# TeensyAmp_R4_2b.net
KiCad netlist of a schematic drawn in EAGLE
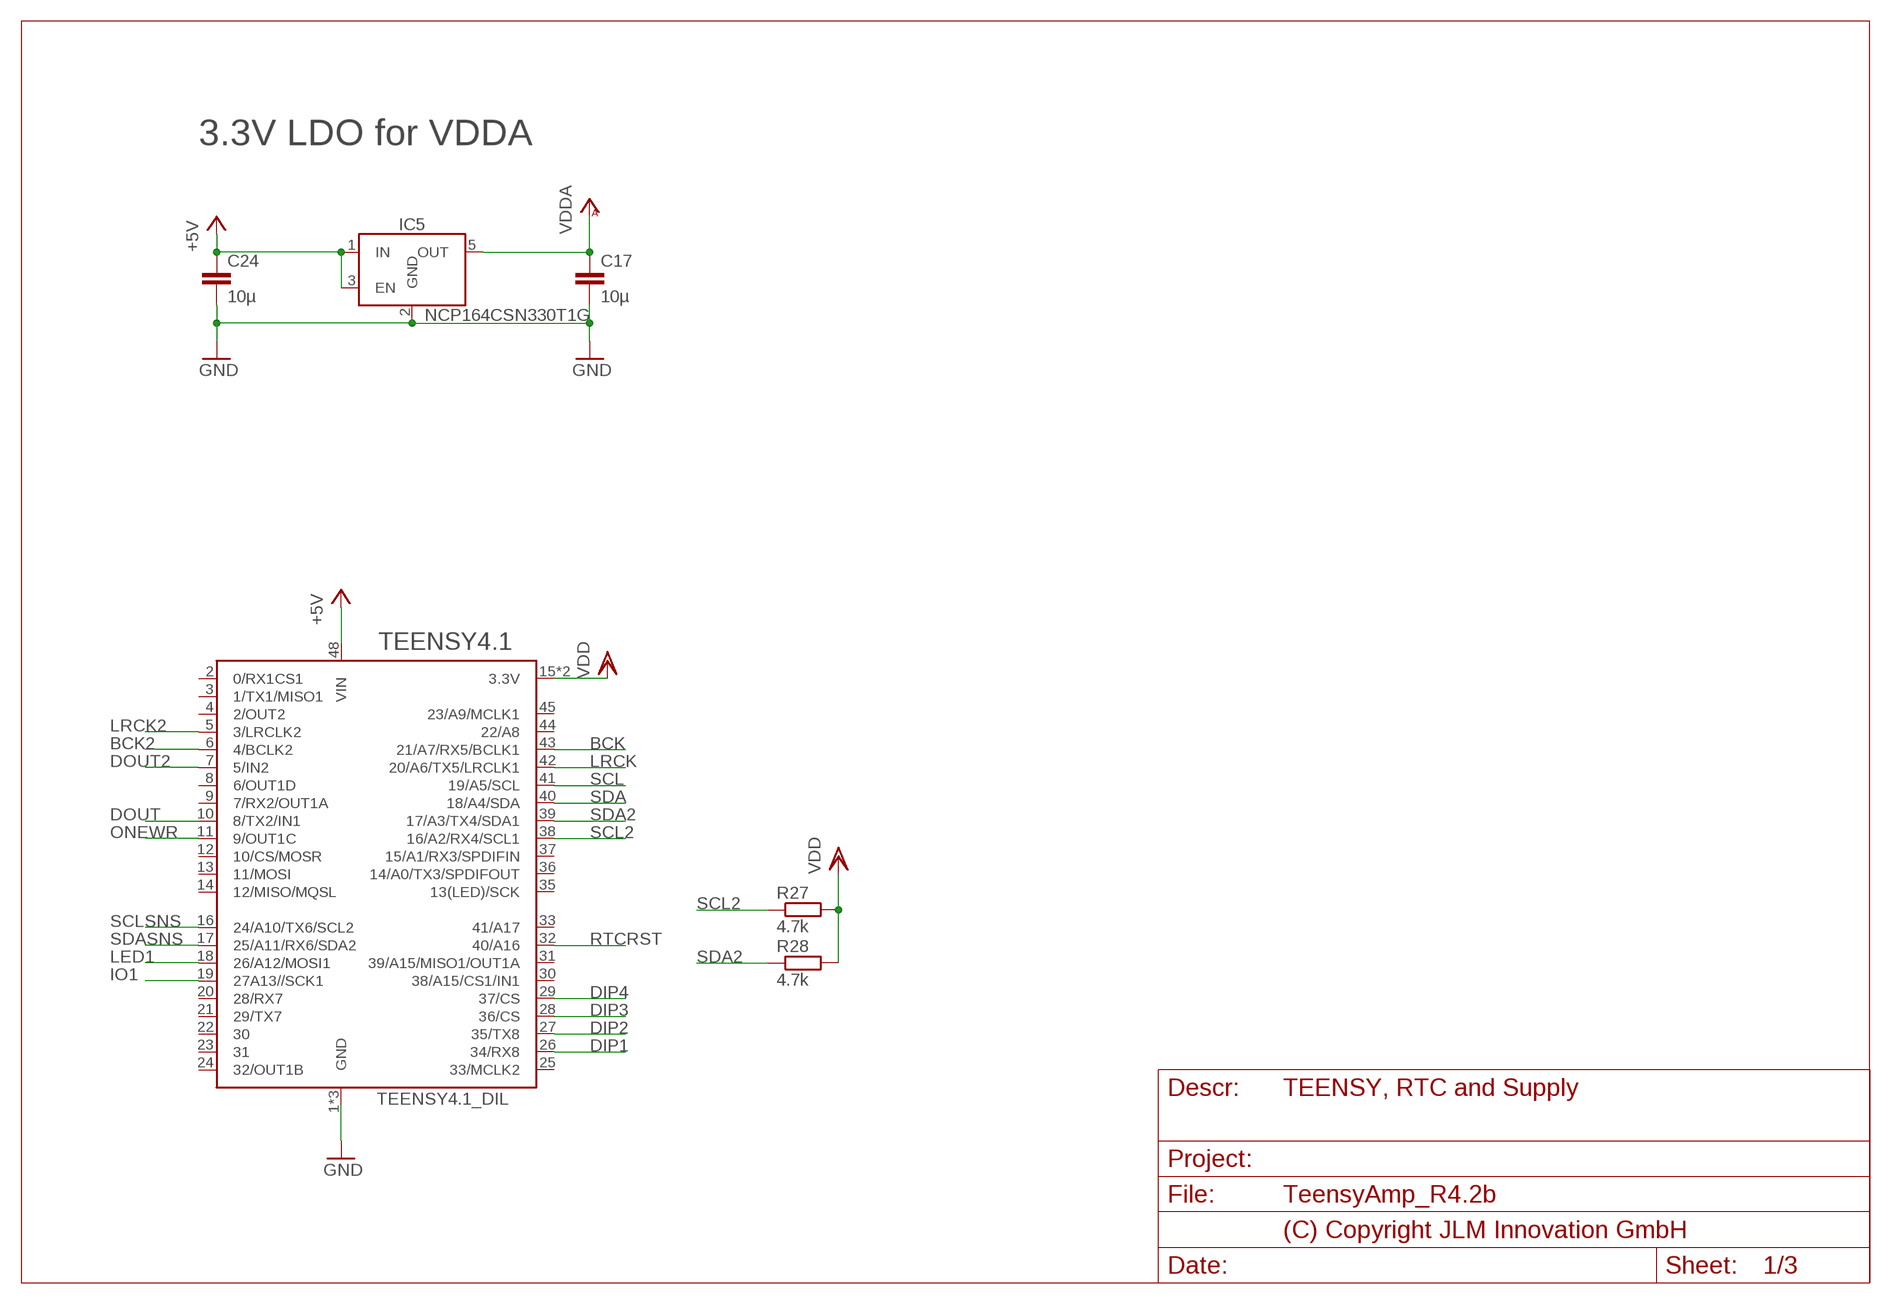
[diagram p0: schematic, sheet 1]
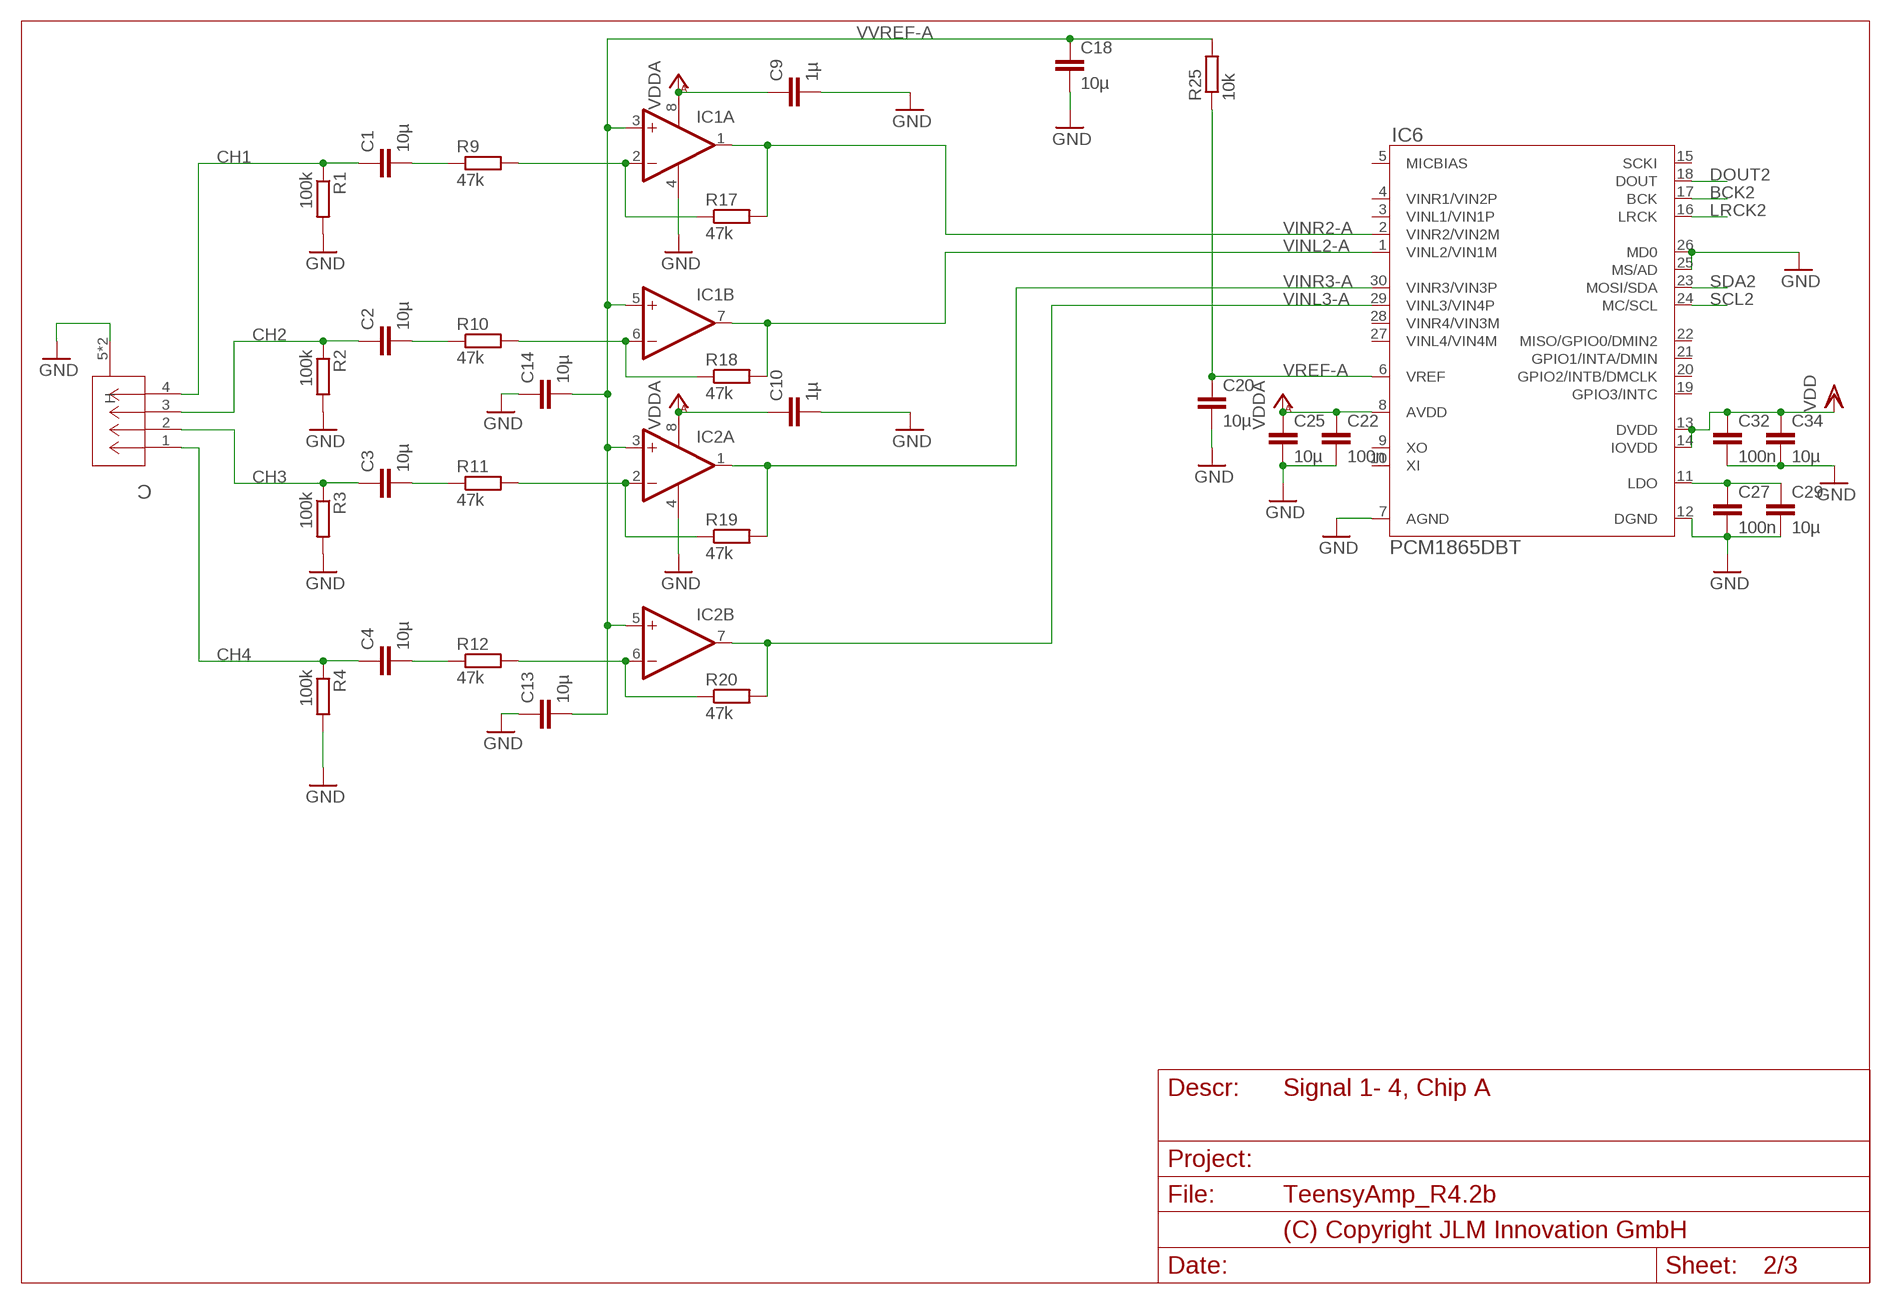
[diagram p1: schematic, sheet 2]
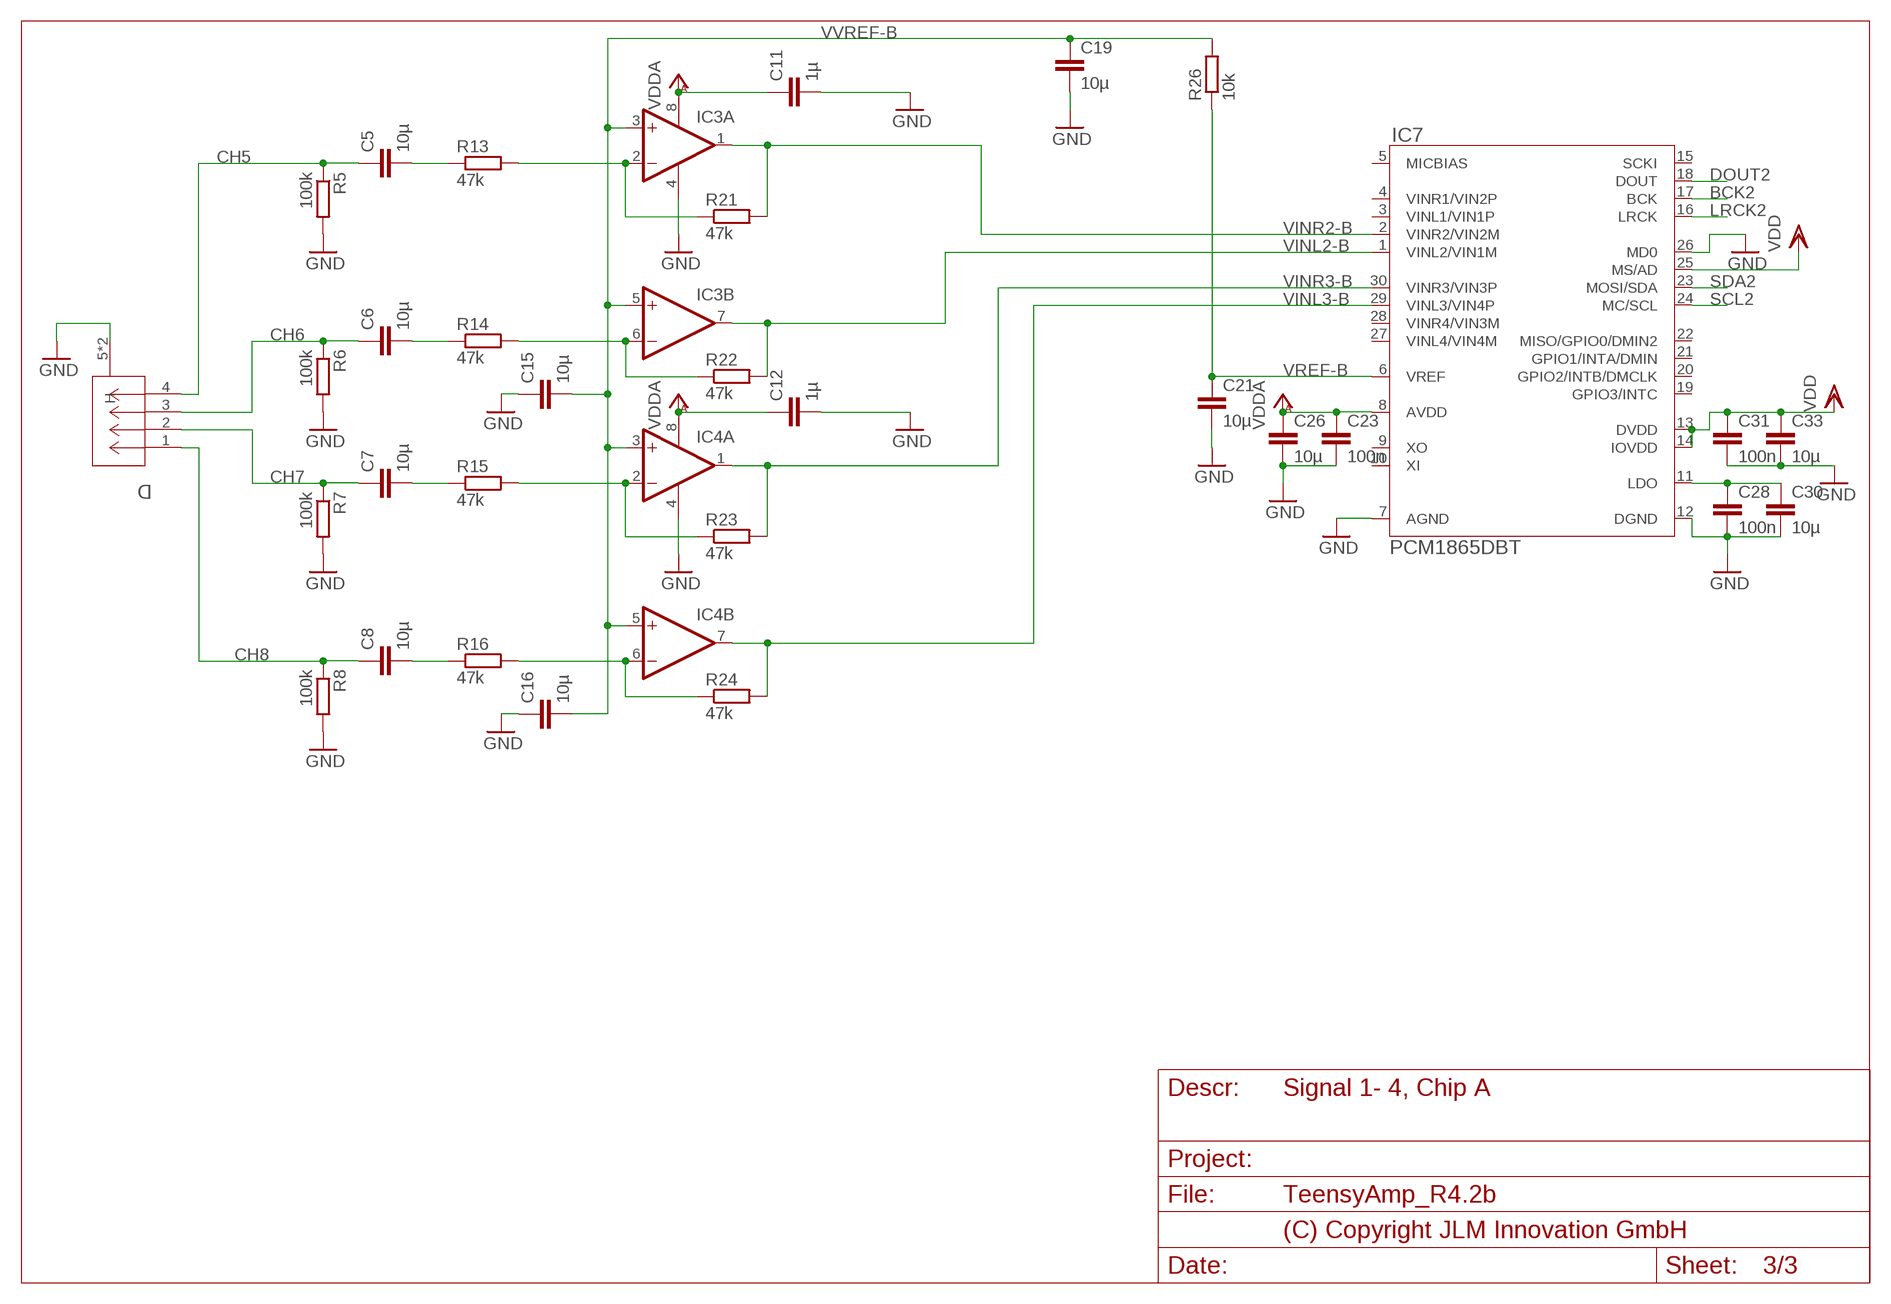
[diagram p2: schematic, sheet 3]

(export (version "E")
  (design (tool "Eeschema 10.0.6"))
  (components
    (comp (ref "C17")
      (value "10µ")
      (footprint "eagle-import:C0603")
      (libsource (lib "eagle-import") (part "C-EUC0603"))
    )
    (comp (ref "C24")
      (value "10µ")
      (footprint "eagle-import:C0603")
      (libsource (lib "eagle-import") (part "C-EUC0603"))
    )
    (comp (ref "IC5")
      (value "NCP164CSN330T1G")
      (footprint "eagle-import:SOT23-5")
      (libsource (lib "eagle-import") (part "LDO_ENSOT23-5"))
    )
    (comp (ref "R27")
      (value "4.7k")
      (footprint "eagle-import:R0603")
      (libsource (lib "eagle-import") (part "R_JLMR0603"))
    )
    (comp (ref "R28")
      (value "4.7k")
      (footprint "eagle-import:R0603")
      (libsource (lib "eagle-import") (part "R_JLMR0603"))
    )
    (comp (ref "TEENSY4.1")
      (value "TEENSY4.1_DIL")
      (footprint "eagle-import:TEENSY4.1_DIL")
      (libsource (lib "eagle-import") (part "TEENSY4.1_DIL"))
    )
    (comp (ref "C")
      (value "5055670471")
      (footprint "eagle-import:CONN04_5055670471_MOL")
      (fields (field (name "COPYRIGHT") "Copyright (C) 2025 Ultra Librarian. All rights reserved."))
      (libsource (lib "eagle-import") (part "5055670471"))
    )
    (comp (ref "C1")
      (value "10µ")
      (footprint "eagle-import:C0805")
      (libsource (lib "eagle-import") (part "C-EUC0805"))
    )
    (comp (ref "C2")
      (value "10µ")
      (footprint "eagle-import:C0805")
      (libsource (lib "eagle-import") (part "C-EUC0805"))
    )
    (comp (ref "C3")
      (value "10µ")
      (footprint "eagle-import:C0805")
      (libsource (lib "eagle-import") (part "C-EUC0805"))
    )
    (comp (ref "C4")
      (value "10µ")
      (footprint "eagle-import:C0805")
      (libsource (lib "eagle-import") (part "C-EUC0805"))
    )
    (comp (ref "C9")
      (value "1µ")
      (footprint "eagle-import:C0603")
      (libsource (lib "eagle-import") (part "C-EUC0603"))
    )
    (comp (ref "C10")
      (value "1µ")
      (footprint "eagle-import:C0603")
      (libsource (lib "eagle-import") (part "C-EUC0603"))
    )
    (comp (ref "C13")
      (value "10µ")
      (footprint "eagle-import:C0603")
      (libsource (lib "eagle-import") (part "C-EUC0603"))
    )
    (comp (ref "C14")
      (value "10µ")
      (footprint "eagle-import:C0603")
      (libsource (lib "eagle-import") (part "C-EUC0603"))
    )
    (comp (ref "C18")
      (value "10µ")
      (footprint "eagle-import:C0603")
      (libsource (lib "eagle-import") (part "C-EUC0603"))
    )
    (comp (ref "C20")
      (value "10µ")
      (footprint "eagle-import:C0603")
      (libsource (lib "eagle-import") (part "C-EUC0603"))
    )
    (comp (ref "C22")
      (value "100n")
      (footprint "eagle-import:C0603")
      (libsource (lib "eagle-import") (part "C-EUC0603"))
    )
    (comp (ref "C25")
      (value "10µ")
      (footprint "eagle-import:C0603")
      (libsource (lib "eagle-import") (part "C-EUC0603"))
    )
    (comp (ref "C27")
      (value "100n")
      (footprint "eagle-import:C0603")
      (libsource (lib "eagle-import") (part "C-EUC0603"))
    )
    (comp (ref "C29")
      (value "10µ")
      (footprint "eagle-import:C0603")
      (libsource (lib "eagle-import") (part "C-EUC0603"))
    )
    (comp (ref "C32")
      (value "100n")
      (footprint "eagle-import:C0603")
      (libsource (lib "eagle-import") (part "C-EUC0603"))
    )
    (comp (ref "C34")
      (value "10µ")
      (footprint "eagle-import:C0603")
      (libsource (lib "eagle-import") (part "C-EUC0603"))
    )
    (comp (ref "IC1")
      (value "OPA2344E")
      (footprint "eagle-import:MSOP08")
      (libsource (lib "eagle-import") (part "OPA2E344"))
    )
    (comp (ref "IC2")
      (value "OPA2344E")
      (footprint "eagle-import:MSOP08")
      (libsource (lib "eagle-import") (part "OPA2E344"))
    )
    (comp (ref "IC6")
      (value "PCM1865DBT")
      (footprint "eagle-import:SOP50P640X120-30N")
      (libsource (lib "eagle-import") (part "PCM1865DBT"))
    )
    (comp (ref "R1")
      (value "100k")
      (footprint "eagle-import:R0603")
      (libsource (lib "eagle-import") (part "R_JLMR0603"))
    )
    (comp (ref "R2")
      (value "100k")
      (footprint "eagle-import:R0603")
      (libsource (lib "eagle-import") (part "R_JLMR0603"))
    )
    (comp (ref "R3")
      (value "100k")
      (footprint "eagle-import:R0603")
      (libsource (lib "eagle-import") (part "R_JLMR0603"))
    )
    (comp (ref "R4")
      (value "100k")
      (footprint "eagle-import:R0603")
      (libsource (lib "eagle-import") (part "R_JLMR0603"))
    )
    (comp (ref "R9")
      (value "47k")
      (footprint "eagle-import:R0603")
      (libsource (lib "eagle-import") (part "R_JLMR0603"))
    )
    (comp (ref "R10")
      (value "47k")
      (footprint "eagle-import:R0603")
      (libsource (lib "eagle-import") (part "R_JLMR0603"))
    )
    (comp (ref "R11")
      (value "47k")
      (footprint "eagle-import:R0603")
      (libsource (lib "eagle-import") (part "R_JLMR0603"))
    )
    (comp (ref "R12")
      (value "47k")
      (footprint "eagle-import:R0603")
      (libsource (lib "eagle-import") (part "R_JLMR0603"))
    )
    (comp (ref "R17")
      (value "47k")
      (footprint "eagle-import:R0603")
      (libsource (lib "eagle-import") (part "R_JLMR0603"))
    )
    (comp (ref "R18")
      (value "47k")
      (footprint "eagle-import:R0603")
      (libsource (lib "eagle-import") (part "R_JLMR0603"))
    )
    (comp (ref "R19")
      (value "47k")
      (footprint "eagle-import:R0603")
      (libsource (lib "eagle-import") (part "R_JLMR0603"))
    )
    (comp (ref "R20")
      (value "47k")
      (footprint "eagle-import:R0603")
      (libsource (lib "eagle-import") (part "R_JLMR0603"))
    )
    (comp (ref "R25")
      (value "10k")
      (footprint "eagle-import:R0603")
      (libsource (lib "eagle-import") (part "R_JLMR0603"))
    )
    (comp (ref "C5")
      (value "10µ")
      (footprint "eagle-import:C0805")
      (libsource (lib "eagle-import") (part "C-EUC0805"))
    )
    (comp (ref "C6")
      (value "10µ")
      (footprint "eagle-import:C0805")
      (libsource (lib "eagle-import") (part "C-EUC0805"))
    )
    (comp (ref "C7")
      (value "10µ")
      (footprint "eagle-import:C0805")
      (libsource (lib "eagle-import") (part "C-EUC0805"))
    )
    (comp (ref "C8")
      (value "10µ")
      (footprint "eagle-import:C0805")
      (libsource (lib "eagle-import") (part "C-EUC0805"))
    )
    (comp (ref "C11")
      (value "1µ")
      (footprint "eagle-import:C0603")
      (libsource (lib "eagle-import") (part "C-EUC0603"))
    )
    (comp (ref "C12")
      (value "1µ")
      (footprint "eagle-import:C0603")
      (libsource (lib "eagle-import") (part "C-EUC0603"))
    )
    (comp (ref "C15")
      (value "10µ")
      (footprint "eagle-import:C0603")
      (libsource (lib "eagle-import") (part "C-EUC0603"))
    )
    (comp (ref "C16")
      (value "10µ")
      (footprint "eagle-import:C0603")
      (libsource (lib "eagle-import") (part "C-EUC0603"))
    )
    (comp (ref "C19")
      (value "10µ")
      (footprint "eagle-import:C0603")
      (libsource (lib "eagle-import") (part "C-EUC0603"))
    )
    (comp (ref "C21")
      (value "10µ")
      (footprint "eagle-import:C0603")
      (libsource (lib "eagle-import") (part "C-EUC0603"))
    )
    (comp (ref "C23")
      (value "100n")
      (footprint "eagle-import:C0603")
      (libsource (lib "eagle-import") (part "C-EUC0603"))
    )
    (comp (ref "C26")
      (value "10µ")
      (footprint "eagle-import:C0603")
      (libsource (lib "eagle-import") (part "C-EUC0603"))
    )
    (comp (ref "C28")
      (value "100n")
      (footprint "eagle-import:C0603")
      (libsource (lib "eagle-import") (part "C-EUC0603"))
    )
    (comp (ref "C30")
      (value "10µ")
      (footprint "eagle-import:C0603")
      (libsource (lib "eagle-import") (part "C-EUC0603"))
    )
    (comp (ref "C31")
      (value "100n")
      (footprint "eagle-import:C0603")
      (libsource (lib "eagle-import") (part "C-EUC0603"))
    )
    (comp (ref "C33")
      (value "10µ")
      (footprint "eagle-import:C0603")
      (libsource (lib "eagle-import") (part "C-EUC0603"))
    )
    (comp (ref "D")
      (value "5055670471")
      (footprint "eagle-import:CONN04_5055670471_MOL")
      (fields (field (name "COPYRIGHT") "Copyright (C) 2025 Ultra Librarian. All rights reserved."))
      (libsource (lib "eagle-import") (part "5055670471"))
    )
    (comp (ref "IC3")
      (value "OPA2344E")
      (footprint "eagle-import:MSOP08")
      (libsource (lib "eagle-import") (part "OPA2E344"))
    )
    (comp (ref "IC4")
      (value "OPA2344E")
      (footprint "eagle-import:MSOP08")
      (libsource (lib "eagle-import") (part "OPA2E344"))
    )
    (comp (ref "IC7")
      (value "PCM1865DBT")
      (footprint "eagle-import:SOP50P640X120-30N")
      (libsource (lib "eagle-import") (part "PCM1865DBT"))
    )
    (comp (ref "R5")
      (value "100k")
      (footprint "eagle-import:R0603")
      (libsource (lib "eagle-import") (part "R_JLMR0603"))
    )
    (comp (ref "R6")
      (value "100k")
      (footprint "eagle-import:R0603")
      (libsource (lib "eagle-import") (part "R_JLMR0603"))
    )
    (comp (ref "R7")
      (value "100k")
      (footprint "eagle-import:R0603")
      (libsource (lib "eagle-import") (part "R_JLMR0603"))
    )
    (comp (ref "R8")
      (value "100k")
      (footprint "eagle-import:R0603")
      (libsource (lib "eagle-import") (part "R_JLMR0603"))
    )
    (comp (ref "R13")
      (value "47k")
      (footprint "eagle-import:R0603")
      (libsource (lib "eagle-import") (part "R_JLMR0603"))
    )
    (comp (ref "R14")
      (value "47k")
      (footprint "eagle-import:R0603")
      (libsource (lib "eagle-import") (part "R_JLMR0603"))
    )
    (comp (ref "R15")
      (value "47k")
      (footprint "eagle-import:R0603")
      (libsource (lib "eagle-import") (part "R_JLMR0603"))
    )
    (comp (ref "R16")
      (value "47k")
      (footprint "eagle-import:R0603")
      (libsource (lib "eagle-import") (part "R_JLMR0603"))
    )
    (comp (ref "R21")
      (value "47k")
      (footprint "eagle-import:R0603")
      (libsource (lib "eagle-import") (part "R_JLMR0603"))
    )
    (comp (ref "R22")
      (value "47k")
      (footprint "eagle-import:R0603")
      (libsource (lib "eagle-import") (part "R_JLMR0603"))
    )
    (comp (ref "R23")
      (value "47k")
      (footprint "eagle-import:R0603")
      (libsource (lib "eagle-import") (part "R_JLMR0603"))
    )
    (comp (ref "R24")
      (value "47k")
      (footprint "eagle-import:R0603")
      (libsource (lib "eagle-import") (part "R_JLMR0603"))
    )
    (comp (ref "R26")
      (value "10k")
      (footprint "eagle-import:R0603")
      (libsource (lib "eagle-import") (part "R_JLMR0603"))
    )
  )
  (nets
    (net (code "1") (name "+5V") (class "Default")
      (node (ref "C24") (pin "1") (pinfunction "1_1") (pintype "passive"))
      (node (ref "IC5") (pin "1") (pinfunction "IN_1") (pintype "input"))
      (node (ref "IC5") (pin "3") (pinfunction "EN_3") (pintype "input"))
      (node (ref "TEENSY4.1") (pin "48") (pinfunction "VIN_48") (pintype "power_in"))
    )
    (net (code "2") (name "BCK") (class "Default")
      (node (ref "TEENSY4.1") (pin "43") (pinfunction "21/A7/RX5/BCLK1_43") (pintype "bidirectional"))
    )
    (net (code "3") (name "BCK2") (class "Default")
      (node (ref "IC6") (pin "17") (pinfunction "BCK_17") (pintype "bidirectional"))
      (node (ref "IC7") (pin "17") (pinfunction "BCK_17") (pintype "bidirectional"))
      (node (ref "TEENSY4.1") (pin "6") (pinfunction "4/BCLK2_6") (pintype "bidirectional"))
    )
    (net (code "4") (name "CH1") (class "Default")
      (node (ref "C") (pin "4") (pinfunction "4_4") (pintype "passive"))
      (node (ref "C1") (pin "1") (pinfunction "1_1") (pintype "passive"))
      (node (ref "R1") (pin "1") (pinfunction "1_1") (pintype "passive"))
    )
    (net (code "5") (name "CH2") (class "Default")
      (node (ref "C") (pin "3") (pinfunction "3_3") (pintype "passive"))
      (node (ref "C2") (pin "1") (pinfunction "1_1") (pintype "passive"))
      (node (ref "R2") (pin "1") (pinfunction "1_1") (pintype "passive"))
    )
    (net (code "6") (name "CH3") (class "Default")
      (node (ref "C") (pin "2") (pinfunction "2_2") (pintype "passive"))
      (node (ref "C3") (pin "1") (pinfunction "1_1") (pintype "passive"))
      (node (ref "R3") (pin "1") (pinfunction "1_1") (pintype "passive"))
    )
    (net (code "7") (name "CH4") (class "Default")
      (node (ref "C") (pin "1") (pinfunction "1_1") (pintype "passive"))
      (node (ref "C4") (pin "1") (pinfunction "1_1") (pintype "passive"))
      (node (ref "R4") (pin "1") (pinfunction "1_1") (pintype "passive"))
    )
    (net (code "8") (name "CH5") (class "Default")
      (node (ref "C5") (pin "1") (pinfunction "1_1") (pintype "passive"))
      (node (ref "D") (pin "4") (pinfunction "4_4") (pintype "passive"))
      (node (ref "R5") (pin "1") (pinfunction "1_1") (pintype "passive"))
    )
    (net (code "9") (name "CH6") (class "Default")
      (node (ref "C6") (pin "1") (pinfunction "1_1") (pintype "passive"))
      (node (ref "D") (pin "3") (pinfunction "3_3") (pintype "passive"))
      (node (ref "R6") (pin "1") (pinfunction "1_1") (pintype "passive"))
    )
    (net (code "10") (name "CH7") (class "Default")
      (node (ref "C7") (pin "1") (pinfunction "1_1") (pintype "passive"))
      (node (ref "D") (pin "2") (pinfunction "2_2") (pintype "passive"))
      (node (ref "R7") (pin "1") (pinfunction "1_1") (pintype "passive"))
    )
    (net (code "11") (name "CH8") (class "Default")
      (node (ref "C8") (pin "1") (pinfunction "1_1") (pintype "passive"))
      (node (ref "D") (pin "1") (pinfunction "1_1") (pintype "passive"))
      (node (ref "R8") (pin "1") (pinfunction "1_1") (pintype "passive"))
    )
    (net (code "12") (name "DIP1") (class "Default")
      (node (ref "TEENSY4.1") (pin "26") (pinfunction "34/RX8_26") (pintype "bidirectional"))
    )
    (net (code "13") (name "DIP2") (class "Default")
      (node (ref "TEENSY4.1") (pin "27") (pinfunction "35/TX8_27") (pintype "bidirectional"))
    )
    (net (code "14") (name "DIP3") (class "Default")
      (node (ref "TEENSY4.1") (pin "28") (pinfunction "36/CS_28") (pintype "bidirectional"))
    )
    (net (code "15") (name "DIP4") (class "Default")
      (node (ref "TEENSY4.1") (pin "29") (pinfunction "37/CS_29") (pintype "bidirectional"))
    )
    (net (code "16") (name "DOUT") (class "Default")
      (node (ref "TEENSY4.1") (pin "10") (pinfunction "8/TX2/IN1_10") (pintype "bidirectional"))
    )
    (net (code "17") (name "DOUT2") (class "Default")
      (node (ref "IC6") (pin "18") (pinfunction "DOUT_18") (pintype "output"))
      (node (ref "IC7") (pin "18") (pinfunction "DOUT_18") (pintype "output"))
      (node (ref "TEENSY4.1") (pin "7") (pinfunction "5/IN2_7") (pintype "bidirectional"))
    )
    (net (code "18") (name "GND") (class "Default")
      (node (ref "C") (pin "5") (pinfunction "H_5") (pintype "passive"))
      (node (ref "C") (pin "6") (pinfunction "H_6") (pintype "passive"))
      (node (ref "C10") (pin "2") (pinfunction "2_2") (pintype "passive"))
      (node (ref "C11") (pin "2") (pinfunction "2_2") (pintype "passive"))
      (node (ref "C12") (pin "2") (pinfunction "2_2") (pintype "passive"))
      (node (ref "C13") (pin "1") (pinfunction "1_1") (pintype "passive"))
      (node (ref "C14") (pin "1") (pinfunction "1_1") (pintype "passive"))
      (node (ref "C15") (pin "1") (pinfunction "1_1") (pintype "passive"))
      (node (ref "C16") (pin "1") (pinfunction "1_1") (pintype "passive"))
      (node (ref "C17") (pin "2") (pinfunction "2_2") (pintype "passive"))
      (node (ref "C18") (pin "2") (pinfunction "2_2") (pintype "passive"))
      (node (ref "C19") (pin "2") (pinfunction "2_2") (pintype "passive"))
      (node (ref "C20") (pin "2") (pinfunction "2_2") (pintype "passive"))
      (node (ref "C21") (pin "2") (pinfunction "2_2") (pintype "passive"))
      (node (ref "C22") (pin "2") (pinfunction "2_2") (pintype "passive"))
      (node (ref "C23") (pin "2") (pinfunction "2_2") (pintype "passive"))
      (node (ref "C24") (pin "2") (pinfunction "2_2") (pintype "passive"))
      (node (ref "C25") (pin "2") (pinfunction "2_2") (pintype "passive"))
      (node (ref "C26") (pin "2") (pinfunction "2_2") (pintype "passive"))
      (node (ref "C27") (pin "2") (pinfunction "2_2") (pintype "passive"))
      (node (ref "C28") (pin "2") (pinfunction "2_2") (pintype "passive"))
      (node (ref "C29") (pin "2") (pinfunction "2_2") (pintype "passive"))
      (node (ref "C30") (pin "2") (pinfunction "2_2") (pintype "passive"))
      (node (ref "C31") (pin "2") (pinfunction "2_2") (pintype "passive"))
      (node (ref "C32") (pin "2") (pinfunction "2_2") (pintype "passive"))
      (node (ref "C33") (pin "2") (pinfunction "2_2") (pintype "passive"))
      (node (ref "C34") (pin "2") (pinfunction "2_2") (pintype "passive"))
      (node (ref "C9") (pin "2") (pinfunction "2_2") (pintype "passive"))
      (node (ref "D") (pin "5") (pinfunction "H_5") (pintype "passive"))
      (node (ref "D") (pin "6") (pinfunction "H_6") (pintype "passive"))
      (node (ref "IC1") (pin "4") (pinfunction "V-_4") (pintype "power_in"))
      (node (ref "IC2") (pin "4") (pinfunction "V-_4") (pintype "power_in"))
      (node (ref "IC3") (pin "4") (pinfunction "V-_4") (pintype "power_in"))
      (node (ref "IC4") (pin "4") (pinfunction "V-_4") (pintype "power_in"))
      (node (ref "IC5") (pin "2") (pinfunction "GND_2") (pintype "power_in"))
      (node (ref "IC6") (pin "12") (pinfunction "DGND_12") (pintype "power_in"))
      (node (ref "IC6") (pin "25") (pinfunction "MS/AD_25") (pintype "input"))
      (node (ref "IC6") (pin "26") (pinfunction "MD0_26") (pintype "input"))
      (node (ref "IC6") (pin "7") (pinfunction "AGND_7") (pintype "power_in"))
      (node (ref "IC7") (pin "12") (pinfunction "DGND_12") (pintype "power_in"))
      (node (ref "IC7") (pin "26") (pinfunction "MD0_26") (pintype "input"))
      (node (ref "IC7") (pin "7") (pinfunction "AGND_7") (pintype "power_in"))
      (node (ref "R1") (pin "2") (pinfunction "2_2") (pintype "passive"))
      (node (ref "R2") (pin "2") (pinfunction "2_2") (pintype "passive"))
      (node (ref "R3") (pin "2") (pinfunction "2_2") (pintype "passive"))
      (node (ref "R4") (pin "2") (pinfunction "2_2") (pintype "passive"))
      (node (ref "R5") (pin "2") (pinfunction "2_2") (pintype "passive"))
      (node (ref "R6") (pin "2") (pinfunction "2_2") (pintype "passive"))
      (node (ref "R7") (pin "2") (pinfunction "2_2") (pintype "passive"))
      (node (ref "R8") (pin "2") (pinfunction "2_2") (pintype "passive"))
      (node (ref "TEENSY4.1") (pin "1") (pinfunction "GND_1") (pintype "power_in"))
      (node (ref "TEENSY4.1") (pin "34") (pinfunction "GND_34") (pintype "power_in"))
      (node (ref "TEENSY4.1") (pin "47") (pinfunction "GND_47") (pintype "power_in"))
    )
    (net (code "19") (name "IO1") (class "Default")
      (node (ref "TEENSY4.1") (pin "19") (pinfunction "27A13//SCK1_19") (pintype "bidirectional"))
    )
    (net (code "20") (name "LED1") (class "Default")
      (node (ref "TEENSY4.1") (pin "18") (pinfunction "26/A12/MOSI1_18") (pintype "bidirectional"))
    )
    (net (code "21") (name "LRCK") (class "Default")
      (node (ref "TEENSY4.1") (pin "42") (pinfunction "20/A6/TX5/LRCLK1_42") (pintype "bidirectional"))
    )
    (net (code "22") (name "LRCK2") (class "Default")
      (node (ref "IC6") (pin "16") (pinfunction "LRCK_16") (pintype "bidirectional"))
      (node (ref "IC7") (pin "16") (pinfunction "LRCK_16") (pintype "bidirectional"))
      (node (ref "TEENSY4.1") (pin "5") (pinfunction "3/LRCLK2_5") (pintype "bidirectional"))
    )
    (net (code "23") (name "Net-(C1-Pad2)") (class "Default")
      (node (ref "C1") (pin "2") (pinfunction "2_2") (pintype "passive"))
      (node (ref "R9") (pin "1") (pinfunction "1_1") (pintype "passive"))
    )
    (net (code "24") (name "Net-(C2-Pad2)") (class "Default")
      (node (ref "C2") (pin "2") (pinfunction "2_2") (pintype "passive"))
      (node (ref "R10") (pin "1") (pinfunction "1_1") (pintype "passive"))
    )
    (net (code "25") (name "Net-(C3-Pad2)") (class "Default")
      (node (ref "C3") (pin "2") (pinfunction "2_2") (pintype "passive"))
      (node (ref "R11") (pin "1") (pinfunction "1_1") (pintype "passive"))
    )
    (net (code "26") (name "Net-(C4-Pad2)") (class "Default")
      (node (ref "C4") (pin "2") (pinfunction "2_2") (pintype "passive"))
      (node (ref "R12") (pin "1") (pinfunction "1_1") (pintype "passive"))
    )
    (net (code "27") (name "Net-(C5-Pad2)") (class "Default")
      (node (ref "C5") (pin "2") (pinfunction "2_2") (pintype "passive"))
      (node (ref "R13") (pin "1") (pinfunction "1_1") (pintype "passive"))
    )
    (net (code "28") (name "Net-(C6-Pad2)") (class "Default")
      (node (ref "C6") (pin "2") (pinfunction "2_2") (pintype "passive"))
      (node (ref "R14") (pin "1") (pinfunction "1_1") (pintype "passive"))
    )
    (net (code "29") (name "Net-(C7-Pad2)") (class "Default")
      (node (ref "C7") (pin "2") (pinfunction "2_2") (pintype "passive"))
      (node (ref "R15") (pin "1") (pinfunction "1_1") (pintype "passive"))
    )
    (net (code "30") (name "Net-(C8-Pad2)") (class "Default")
      (node (ref "C8") (pin "2") (pinfunction "2_2") (pintype "passive"))
      (node (ref "R16") (pin "1") (pinfunction "1_1") (pintype "passive"))
    )
    (net (code "31") (name "Net-(IC1A--IN)") (class "Default")
      (node (ref "IC1") (pin "2") (pinfunction "-IN_2") (pintype "input"))
      (node (ref "R17") (pin "1") (pinfunction "1_1") (pintype "passive"))
      (node (ref "R9") (pin "2") (pinfunction "2_2") (pintype "passive"))
    )
    (net (code "32") (name "Net-(IC1B--IN)") (class "Default")
      (node (ref "IC1") (pin "6") (pinfunction "-IN_6") (pintype "input"))
      (node (ref "R10") (pin "2") (pinfunction "2_2") (pintype "passive"))
      (node (ref "R18") (pin "1") (pinfunction "1_1") (pintype "passive"))
    )
    (net (code "33") (name "Net-(IC2A--IN)") (class "Default")
      (node (ref "IC2") (pin "2") (pinfunction "-IN_2") (pintype "input"))
      (node (ref "R11") (pin "2") (pinfunction "2_2") (pintype "passive"))
      (node (ref "R19") (pin "1") (pinfunction "1_1") (pintype "passive"))
    )
    (net (code "34") (name "Net-(IC2B--IN)") (class "Default")
      (node (ref "IC2") (pin "6") (pinfunction "-IN_6") (pintype "input"))
      (node (ref "R12") (pin "2") (pinfunction "2_2") (pintype "passive"))
      (node (ref "R20") (pin "1") (pinfunction "1_1") (pintype "passive"))
    )
    (net (code "35") (name "Net-(IC3A--IN)") (class "Default")
      (node (ref "IC3") (pin "2") (pinfunction "-IN_2") (pintype "input"))
      (node (ref "R13") (pin "2") (pinfunction "2_2") (pintype "passive"))
      (node (ref "R21") (pin "1") (pinfunction "1_1") (pintype "passive"))
    )
    (net (code "36") (name "Net-(IC3B--IN)") (class "Default")
      (node (ref "IC3") (pin "6") (pinfunction "-IN_6") (pintype "input"))
      (node (ref "R14") (pin "2") (pinfunction "2_2") (pintype "passive"))
      (node (ref "R22") (pin "1") (pinfunction "1_1") (pintype "passive"))
    )
    (net (code "37") (name "Net-(IC4A--IN)") (class "Default")
      (node (ref "IC4") (pin "2") (pinfunction "-IN_2") (pintype "input"))
      (node (ref "R15") (pin "2") (pinfunction "2_2") (pintype "passive"))
      (node (ref "R23") (pin "1") (pinfunction "1_1") (pintype "passive"))
    )
    (net (code "38") (name "Net-(IC4B--IN)") (class "Default")
      (node (ref "IC4") (pin "6") (pinfunction "-IN_6") (pintype "input"))
      (node (ref "R16") (pin "2") (pinfunction "2_2") (pintype "passive"))
      (node (ref "R24") (pin "1") (pinfunction "1_1") (pintype "passive"))
    )
    (net (code "39") (name "Net-(IC6-LDO)") (class "Default")
      (node (ref "C27") (pin "1") (pinfunction "1_1") (pintype "passive"))
      (node (ref "C29") (pin "1") (pinfunction "1_1") (pintype "passive"))
      (node (ref "IC6") (pin "11") (pinfunction "LDO_11") (pintype "bidirectional"))
    )
    (net (code "40") (name "Net-(IC7-LDO)") (class "Default")
      (node (ref "C28") (pin "1") (pinfunction "1_1") (pintype "passive"))
      (node (ref "C30") (pin "1") (pinfunction "1_1") (pintype "passive"))
      (node (ref "IC7") (pin "11") (pinfunction "LDO_11") (pintype "bidirectional"))
    )
    (net (code "41") (name "ONEWR") (class "Default")
      (node (ref "TEENSY4.1") (pin "11") (pinfunction "9/OUT1C_11") (pintype "bidirectional"))
    )
    (net (code "42") (name "RTCRST") (class "Default")
      (node (ref "TEENSY4.1") (pin "32") (pinfunction "40/A16_32") (pintype "bidirectional"))
    )
    (net (code "43") (name "SCL") (class "Default")
      (node (ref "TEENSY4.1") (pin "41") (pinfunction "19/A5/SCL_41") (pintype "bidirectional"))
    )
    (net (code "44") (name "SCL2") (class "Default")
      (node (ref "IC6") (pin "24") (pinfunction "MC/SCL_24") (pintype "input"))
      (node (ref "IC7") (pin "24") (pinfunction "MC/SCL_24") (pintype "input"))
      (node (ref "R27") (pin "1") (pinfunction "1_1") (pintype "passive"))
      (node (ref "TEENSY4.1") (pin "38") (pinfunction "16/A2/RX4/SCL1_38") (pintype "bidirectional"))
    )
    (net (code "45") (name "SCLSNS") (class "Default")
      (node (ref "TEENSY4.1") (pin "16") (pinfunction "24/A10/TX6/SCL2_16") (pintype "bidirectional"))
    )
    (net (code "46") (name "SDA") (class "Default")
      (node (ref "TEENSY4.1") (pin "40") (pinfunction "18/A4/SDA_40") (pintype "bidirectional"))
    )
    (net (code "47") (name "SDA2") (class "Default")
      (node (ref "IC6") (pin "23") (pinfunction "MOSI/SDA_23") (pintype "bidirectional"))
      (node (ref "IC7") (pin "23") (pinfunction "MOSI/SDA_23") (pintype "bidirectional"))
      (node (ref "R28") (pin "1") (pinfunction "1_1") (pintype "passive"))
      (node (ref "TEENSY4.1") (pin "39") (pinfunction "17/A3/TX4/SDA1_39") (pintype "bidirectional"))
    )
    (net (code "48") (name "SDASNS") (class "Default")
      (node (ref "TEENSY4.1") (pin "17") (pinfunction "25/A11/RX6/SDA2_17") (pintype "bidirectional"))
    )
    (net (code "49") (name "VDD") (class "Default")
      (node (ref "C31") (pin "1") (pinfunction "1_1") (pintype "passive"))
      (node (ref "C32") (pin "1") (pinfunction "1_1") (pintype "passive"))
      (node (ref "C33") (pin "1") (pinfunction "1_1") (pintype "passive"))
      (node (ref "C34") (pin "1") (pinfunction "1_1") (pintype "passive"))
      (node (ref "IC6") (pin "13") (pinfunction "DVDD_13") (pintype "power_in"))
      (node (ref "IC6") (pin "14") (pinfunction "IOVDD_14") (pintype "power_in"))
      (node (ref "IC7") (pin "13") (pinfunction "DVDD_13") (pintype "power_in"))
      (node (ref "IC7") (pin "14") (pinfunction "IOVDD_14") (pintype "power_in"))
      (node (ref "IC7") (pin "25") (pinfunction "MS/AD_25") (pintype "input"))
      (node (ref "R27") (pin "2") (pinfunction "2_2") (pintype "passive"))
      (node (ref "R28") (pin "2") (pinfunction "2_2") (pintype "passive"))
      (node (ref "TEENSY4.1") (pin "15") (pinfunction "3.3V_15") (pintype "output"))
      (node (ref "TEENSY4.1") (pin "46") (pinfunction "3.3V_46") (pintype "output"))
    )
    (net (code "50") (name "VDDA") (class "Default")
      (node (ref "C10") (pin "1") (pinfunction "1_1") (pintype "passive"))
      (node (ref "C11") (pin "1") (pinfunction "1_1") (pintype "passive"))
      (node (ref "C12") (pin "1") (pinfunction "1_1") (pintype "passive"))
      (node (ref "C17") (pin "1") (pinfunction "1_1") (pintype "passive"))
      (node (ref "C22") (pin "1") (pinfunction "1_1") (pintype "passive"))
      (node (ref "C23") (pin "1") (pinfunction "1_1") (pintype "passive"))
      (node (ref "C25") (pin "1") (pinfunction "1_1") (pintype "passive"))
      (node (ref "C26") (pin "1") (pinfunction "1_1") (pintype "passive"))
      (node (ref "C9") (pin "1") (pinfunction "1_1") (pintype "passive"))
      (node (ref "IC1") (pin "8") (pinfunction "V+_8") (pintype "power_in"))
      (node (ref "IC2") (pin "8") (pinfunction "V+_8") (pintype "power_in"))
      (node (ref "IC3") (pin "8") (pinfunction "V+_8") (pintype "power_in"))
      (node (ref "IC4") (pin "8") (pinfunction "V+_8") (pintype "power_in"))
      (node (ref "IC5") (pin "5") (pinfunction "OUT_5") (pintype "output"))
      (node (ref "IC6") (pin "8") (pinfunction "AVDD_8") (pintype "power_in"))
      (node (ref "IC7") (pin "8") (pinfunction "AVDD_8") (pintype "power_in"))
    )
    (net (code "51") (name "VINL2-A") (class "Default")
      (node (ref "IC1") (pin "7") (pinfunction "OUT_7") (pintype "output"))
      (node (ref "IC6") (pin "1") (pinfunction "VINL2/VIN1M_1") (pintype "input"))
      (node (ref "R18") (pin "2") (pinfunction "2_2") (pintype "passive"))
    )
    (net (code "52") (name "VINL2-B") (class "Default")
      (node (ref "IC3") (pin "7") (pinfunction "OUT_7") (pintype "output"))
      (node (ref "IC7") (pin "1") (pinfunction "VINL2/VIN1M_1") (pintype "input"))
      (node (ref "R22") (pin "2") (pinfunction "2_2") (pintype "passive"))
    )
    (net (code "53") (name "VINL3-A") (class "Default")
      (node (ref "IC2") (pin "7") (pinfunction "OUT_7") (pintype "output"))
      (node (ref "IC6") (pin "29") (pinfunction "VINL3/VIN4P_29") (pintype "input"))
      (node (ref "R20") (pin "2") (pinfunction "2_2") (pintype "passive"))
    )
    (net (code "54") (name "VINL3-B") (class "Default")
      (node (ref "IC4") (pin "7") (pinfunction "OUT_7") (pintype "output"))
      (node (ref "IC7") (pin "29") (pinfunction "VINL3/VIN4P_29") (pintype "input"))
      (node (ref "R24") (pin "2") (pinfunction "2_2") (pintype "passive"))
    )
    (net (code "55") (name "VINR2-A") (class "Default")
      (node (ref "IC1") (pin "1") (pinfunction "OUT_1") (pintype "output"))
      (node (ref "IC6") (pin "2") (pinfunction "VINR2/VIN2M_2") (pintype "input"))
      (node (ref "R17") (pin "2") (pinfunction "2_2") (pintype "passive"))
    )
    (net (code "56") (name "VINR2-B") (class "Default")
      (node (ref "IC3") (pin "1") (pinfunction "OUT_1") (pintype "output"))
      (node (ref "IC7") (pin "2") (pinfunction "VINR2/VIN2M_2") (pintype "input"))
      (node (ref "R21") (pin "2") (pinfunction "2_2") (pintype "passive"))
    )
    (net (code "57") (name "VINR3-A") (class "Default")
      (node (ref "IC2") (pin "1") (pinfunction "OUT_1") (pintype "output"))
      (node (ref "IC6") (pin "30") (pinfunction "VINR3/VIN3P_30") (pintype "input"))
      (node (ref "R19") (pin "2") (pinfunction "2_2") (pintype "passive"))
    )
    (net (code "58") (name "VINR3-B") (class "Default")
      (node (ref "IC4") (pin "1") (pinfunction "OUT_1") (pintype "output"))
      (node (ref "IC7") (pin "30") (pinfunction "VINR3/VIN3P_30") (pintype "input"))
      (node (ref "R23") (pin "2") (pinfunction "2_2") (pintype "passive"))
    )
    (net (code "59") (name "VREF-A") (class "Default")
      (node (ref "C20") (pin "1") (pinfunction "1_1") (pintype "passive"))
      (node (ref "IC6") (pin "6") (pinfunction "VREF_6") (pintype "output"))
      (node (ref "R25") (pin "1") (pinfunction "1_1") (pintype "passive"))
    )
    (net (code "60") (name "VREF-B") (class "Default")
      (node (ref "C21") (pin "1") (pinfunction "1_1") (pintype "passive"))
      (node (ref "IC7") (pin "6") (pinfunction "VREF_6") (pintype "output"))
      (node (ref "R26") (pin "1") (pinfunction "1_1") (pintype "passive"))
    )
    (net (code "61") (name "VVREF-A") (class "Default")
      (node (ref "C13") (pin "2") (pinfunction "2_2") (pintype "passive"))
      (node (ref "C14") (pin "2") (pinfunction "2_2") (pintype "passive"))
      (node (ref "C18") (pin "1") (pinfunction "1_1") (pintype "passive"))
      (node (ref "IC1") (pin "3") (pinfunction "+IN_3") (pintype "input"))
      (node (ref "IC1") (pin "5") (pinfunction "+IN_5") (pintype "input"))
      (node (ref "IC2") (pin "3") (pinfunction "+IN_3") (pintype "input"))
      (node (ref "IC2") (pin "5") (pinfunction "+IN_5") (pintype "input"))
      (node (ref "R25") (pin "2") (pinfunction "2_2") (pintype "passive"))
    )
    (net (code "62") (name "VVREF-B") (class "Default")
      (node (ref "C15") (pin "2") (pinfunction "2_2") (pintype "passive"))
      (node (ref "C16") (pin "2") (pinfunction "2_2") (pintype "passive"))
      (node (ref "C19") (pin "1") (pinfunction "1_1") (pintype "passive"))
      (node (ref "IC3") (pin "3") (pinfunction "+IN_3") (pintype "input"))
      (node (ref "IC3") (pin "5") (pinfunction "+IN_5") (pintype "input"))
      (node (ref "IC4") (pin "3") (pinfunction "+IN_3") (pintype "input"))
      (node (ref "IC4") (pin "5") (pinfunction "+IN_5") (pintype "input"))
      (node (ref "R26") (pin "2") (pinfunction "2_2") (pintype "passive"))
    )
    (net (code "63") (name "unconnected-(IC6-GPIO1{slash}INTA{slash}DMIN-Pad21)") (class "Default")
      (node (ref "IC6") (pin "21") (pinfunction "GPIO1/INTA/DMIN_21") (pintype "bidirectional"))
    )
    (net (code "64") (name "unconnected-(IC6-GPIO2{slash}INTB{slash}DMCLK-Pad20)") (class "Default")
      (node (ref "IC6") (pin "20") (pinfunction "GPIO2/INTB/DMCLK_20") (pintype "bidirectional"))
    )
    (net (code "65") (name "unconnected-(IC6-GPIO3{slash}INTC-Pad19)") (class "Default")
      (node (ref "IC6") (pin "19") (pinfunction "GPIO3/INTC_19") (pintype "bidirectional"))
    )
    (net (code "66") (name "unconnected-(IC6-MICBIAS-Pad5)") (class "Default")
      (node (ref "IC6") (pin "5") (pinfunction "MICBIAS_5") (pintype "input"))
    )
    (net (code "67") (name "unconnected-(IC6-MISO{slash}GPIO0{slash}DMIN2-Pad22)") (class "Default")
      (node (ref "IC6") (pin "22") (pinfunction "MISO/GPIO0/DMIN2_22") (pintype "bidirectional"))
    )
    (net (code "68") (name "unconnected-(IC6-SCKI-Pad15)") (class "Default")
      (node (ref "IC6") (pin "15") (pinfunction "SCKI_15") (pintype "input"))
    )
    (net (code "69") (name "unconnected-(IC6-VINL1{slash}VIN1P-Pad3)") (class "Default")
      (node (ref "IC6") (pin "3") (pinfunction "VINL1/VIN1P_3") (pintype "input"))
    )
    (net (code "70") (name "unconnected-(IC6-VINL4{slash}VIN4M-Pad27)") (class "Default")
      (node (ref "IC6") (pin "27") (pinfunction "VINL4/VIN4M_27") (pintype "input"))
    )
    (net (code "71") (name "unconnected-(IC6-VINR1{slash}VIN2P-Pad4)") (class "Default")
      (node (ref "IC6") (pin "4") (pinfunction "VINR1/VIN2P_4") (pintype "input"))
    )
    (net (code "72") (name "unconnected-(IC6-VINR4{slash}VIN3M-Pad28)") (class "Default")
      (node (ref "IC6") (pin "28") (pinfunction "VINR4/VIN3M_28") (pintype "input"))
    )
    (net (code "73") (name "unconnected-(IC6-XI-Pad10)") (class "Default")
      (node (ref "IC6") (pin "10") (pinfunction "XI_10") (pintype "input"))
    )
    (net (code "74") (name "unconnected-(IC6-XO-Pad9)") (class "Default")
      (node (ref "IC6") (pin "9") (pinfunction "XO_9") (pintype "output"))
    )
    (net (code "75") (name "unconnected-(IC7-GPIO1{slash}INTA{slash}DMIN-Pad21)") (class "Default")
      (node (ref "IC7") (pin "21") (pinfunction "GPIO1/INTA/DMIN_21") (pintype "bidirectional"))
    )
    (net (code "76") (name "unconnected-(IC7-GPIO2{slash}INTB{slash}DMCLK-Pad20)") (class "Default")
      (node (ref "IC7") (pin "20") (pinfunction "GPIO2/INTB/DMCLK_20") (pintype "bidirectional"))
    )
    (net (code "77") (name "unconnected-(IC7-GPIO3{slash}INTC-Pad19)") (class "Default")
      (node (ref "IC7") (pin "19") (pinfunction "GPIO3/INTC_19") (pintype "bidirectional"))
    )
    (net (code "78") (name "unconnected-(IC7-MICBIAS-Pad5)") (class "Default")
      (node (ref "IC7") (pin "5") (pinfunction "MICBIAS_5") (pintype "input"))
    )
    (net (code "79") (name "unconnected-(IC7-MISO{slash}GPIO0{slash}DMIN2-Pad22)") (class "Default")
      (node (ref "IC7") (pin "22") (pinfunction "MISO/GPIO0/DMIN2_22") (pintype "bidirectional"))
    )
    (net (code "80") (name "unconnected-(IC7-SCKI-Pad15)") (class "Default")
      (node (ref "IC7") (pin "15") (pinfunction "SCKI_15") (pintype "input"))
    )
    (net (code "81") (name "unconnected-(IC7-VINL1{slash}VIN1P-Pad3)") (class "Default")
      (node (ref "IC7") (pin "3") (pinfunction "VINL1/VIN1P_3") (pintype "input"))
    )
    (net (code "82") (name "unconnected-(IC7-VINL4{slash}VIN4M-Pad27)") (class "Default")
      (node (ref "IC7") (pin "27") (pinfunction "VINL4/VIN4M_27") (pintype "input"))
    )
    (net (code "83") (name "unconnected-(IC7-VINR1{slash}VIN2P-Pad4)") (class "Default")
      (node (ref "IC7") (pin "4") (pinfunction "VINR1/VIN2P_4") (pintype "input"))
    )
    (net (code "84") (name "unconnected-(IC7-VINR4{slash}VIN3M-Pad28)") (class "Default")
      (node (ref "IC7") (pin "28") (pinfunction "VINR4/VIN3M_28") (pintype "input"))
    )
    (net (code "85") (name "unconnected-(IC7-XI-Pad10)") (class "Default")
      (node (ref "IC7") (pin "10") (pinfunction "XI_10") (pintype "input"))
    )
    (net (code "86") (name "unconnected-(IC7-XO-Pad9)") (class "Default")
      (node (ref "IC7") (pin "9") (pinfunction "XO_9") (pintype "output"))
    )
    (net (code "87") (name "unconnected-(TEENSY4.1-0{slash}RX1CS1-Pad2)") (class "Default")
      (node (ref "TEENSY4.1") (pin "2") (pinfunction "0/RX1CS1_2") (pintype "bidirectional"))
    )
    (net (code "88") (name "unconnected-(TEENSY4.1-1{slash}TX1{slash}MISO1-Pad3)") (class "Default")
      (node (ref "TEENSY4.1") (pin "3") (pinfunction "1/TX1/MISO1_3") (pintype "bidirectional"))
    )
    (net (code "89") (name "unconnected-(TEENSY4.1-2{slash}OUT2-Pad4)") (class "Default")
      (node (ref "TEENSY4.1") (pin "4") (pinfunction "2/OUT2_4") (pintype "bidirectional"))
    )
    (net (code "90") (name "unconnected-(TEENSY4.1-6{slash}OUT1D-Pad8)") (class "Default")
      (node (ref "TEENSY4.1") (pin "8") (pinfunction "6/OUT1D_8") (pintype "bidirectional"))
    )
    (net (code "91") (name "unconnected-(TEENSY4.1-7{slash}RX2{slash}OUT1A-Pad9)") (class "Default")
      (node (ref "TEENSY4.1") (pin "9") (pinfunction "7/RX2/OUT1A_9") (pintype "bidirectional"))
    )
    (net (code "92") (name "unconnected-(TEENSY4.1-10{slash}CS{slash}MOSR-Pad12)") (class "Default")
      (node (ref "TEENSY4.1") (pin "12") (pinfunction "10/CS/MOSR_12") (pintype "bidirectional"))
    )
    (net (code "93") (name "unconnected-(TEENSY4.1-11{slash}MOSI-Pad13)") (class "Default")
      (node (ref "TEENSY4.1") (pin "13") (pinfunction "11/MOSI_13") (pintype "bidirectional"))
    )
    (net (code "94") (name "unconnected-(TEENSY4.1-12{slash}MISO{slash}MQSL-Pad14)") (class "Default")
      (node (ref "TEENSY4.1") (pin "14") (pinfunction "12/MISO/MQSL_14") (pintype "bidirectional"))
    )
    (net (code "95") (name "unconnected-(TEENSY4.1-13(LED){slash}SCK-Pad35)") (class "Default")
      (node (ref "TEENSY4.1") (pin "35") (pinfunction "13(LED)/SCK_35") (pintype "bidirectional"))
    )
    (net (code "96") (name "unconnected-(TEENSY4.1-14{slash}A0{slash}TX3{slash}SPDIFOUT-Pad36)") (class "Default")
      (node (ref "TEENSY4.1") (pin "36") (pinfunction "14/A0/TX3/SPDIFOUT_36") (pintype "bidirectional"))
    )
    (net (code "97") (name "unconnected-(TEENSY4.1-15{slash}A1{slash}RX3{slash}SPDIFIN-Pad37)") (class "Default")
      (node (ref "TEENSY4.1") (pin "37") (pinfunction "15/A1/RX3/SPDIFIN_37") (pintype "bidirectional"))
    )
    (net (code "98") (name "unconnected-(TEENSY4.1-22{slash}A8-Pad44)") (class "Default")
      (node (ref "TEENSY4.1") (pin "44") (pinfunction "22/A8_44") (pintype "bidirectional"))
    )
    (net (code "99") (name "unconnected-(TEENSY4.1-23{slash}A9{slash}MCLK1-Pad45)") (class "Default")
      (node (ref "TEENSY4.1") (pin "45") (pinfunction "23/A9/MCLK1_45") (pintype "bidirectional"))
    )
    (net (code "100") (name "unconnected-(TEENSY4.1-28{slash}RX7-Pad20)") (class "Default")
      (node (ref "TEENSY4.1") (pin "20") (pinfunction "28/RX7_20") (pintype "bidirectional"))
    )
    (net (code "101") (name "unconnected-(TEENSY4.1-29{slash}TX7-Pad21)") (class "Default")
      (node (ref "TEENSY4.1") (pin "21") (pinfunction "29/TX7_21") (pintype "bidirectional"))
    )
    (net (code "102") (name "unconnected-(TEENSY4.1-30-Pad22)") (class "Default")
      (node (ref "TEENSY4.1") (pin "22") (pinfunction "30_22") (pintype "bidirectional"))
    )
    (net (code "103") (name "unconnected-(TEENSY4.1-31-Pad23)") (class "Default")
      (node (ref "TEENSY4.1") (pin "23") (pinfunction "31_23") (pintype "bidirectional"))
    )
    (net (code "104") (name "unconnected-(TEENSY4.1-32{slash}OUT1B-Pad24)") (class "Default")
      (node (ref "TEENSY4.1") (pin "24") (pinfunction "32/OUT1B_24") (pintype "bidirectional"))
    )
    (net (code "105") (name "unconnected-(TEENSY4.1-33{slash}MCLK2-Pad25)") (class "Default")
      (node (ref "TEENSY4.1") (pin "25") (pinfunction "33/MCLK2_25") (pintype "bidirectional"))
    )
    (net (code "106") (name "unconnected-(TEENSY4.1-38{slash}A15{slash}CS1{slash}IN1-Pad30)") (class "Default")
      (node (ref "TEENSY4.1") (pin "30") (pinfunction "38/A15/CS1/IN1_30") (pintype "bidirectional"))
    )
    (net (code "107") (name "unconnected-(TEENSY4.1-39{slash}A15{slash}MISO1{slash}OUT1A-Pad31)") (class "Default")
      (node (ref "TEENSY4.1") (pin "31") (pinfunction "39/A15/MISO1/OUT1A_31") (pintype "bidirectional"))
    )
    (net (code "108") (name "unconnected-(TEENSY4.1-41{slash}A17-Pad33)") (class "Default")
      (node (ref "TEENSY4.1") (pin "33") (pinfunction "41/A17_33") (pintype "bidirectional"))
    )
  )
)
